# uC_Board.net
KiCad netlist of a schematic drawn in EAGLE
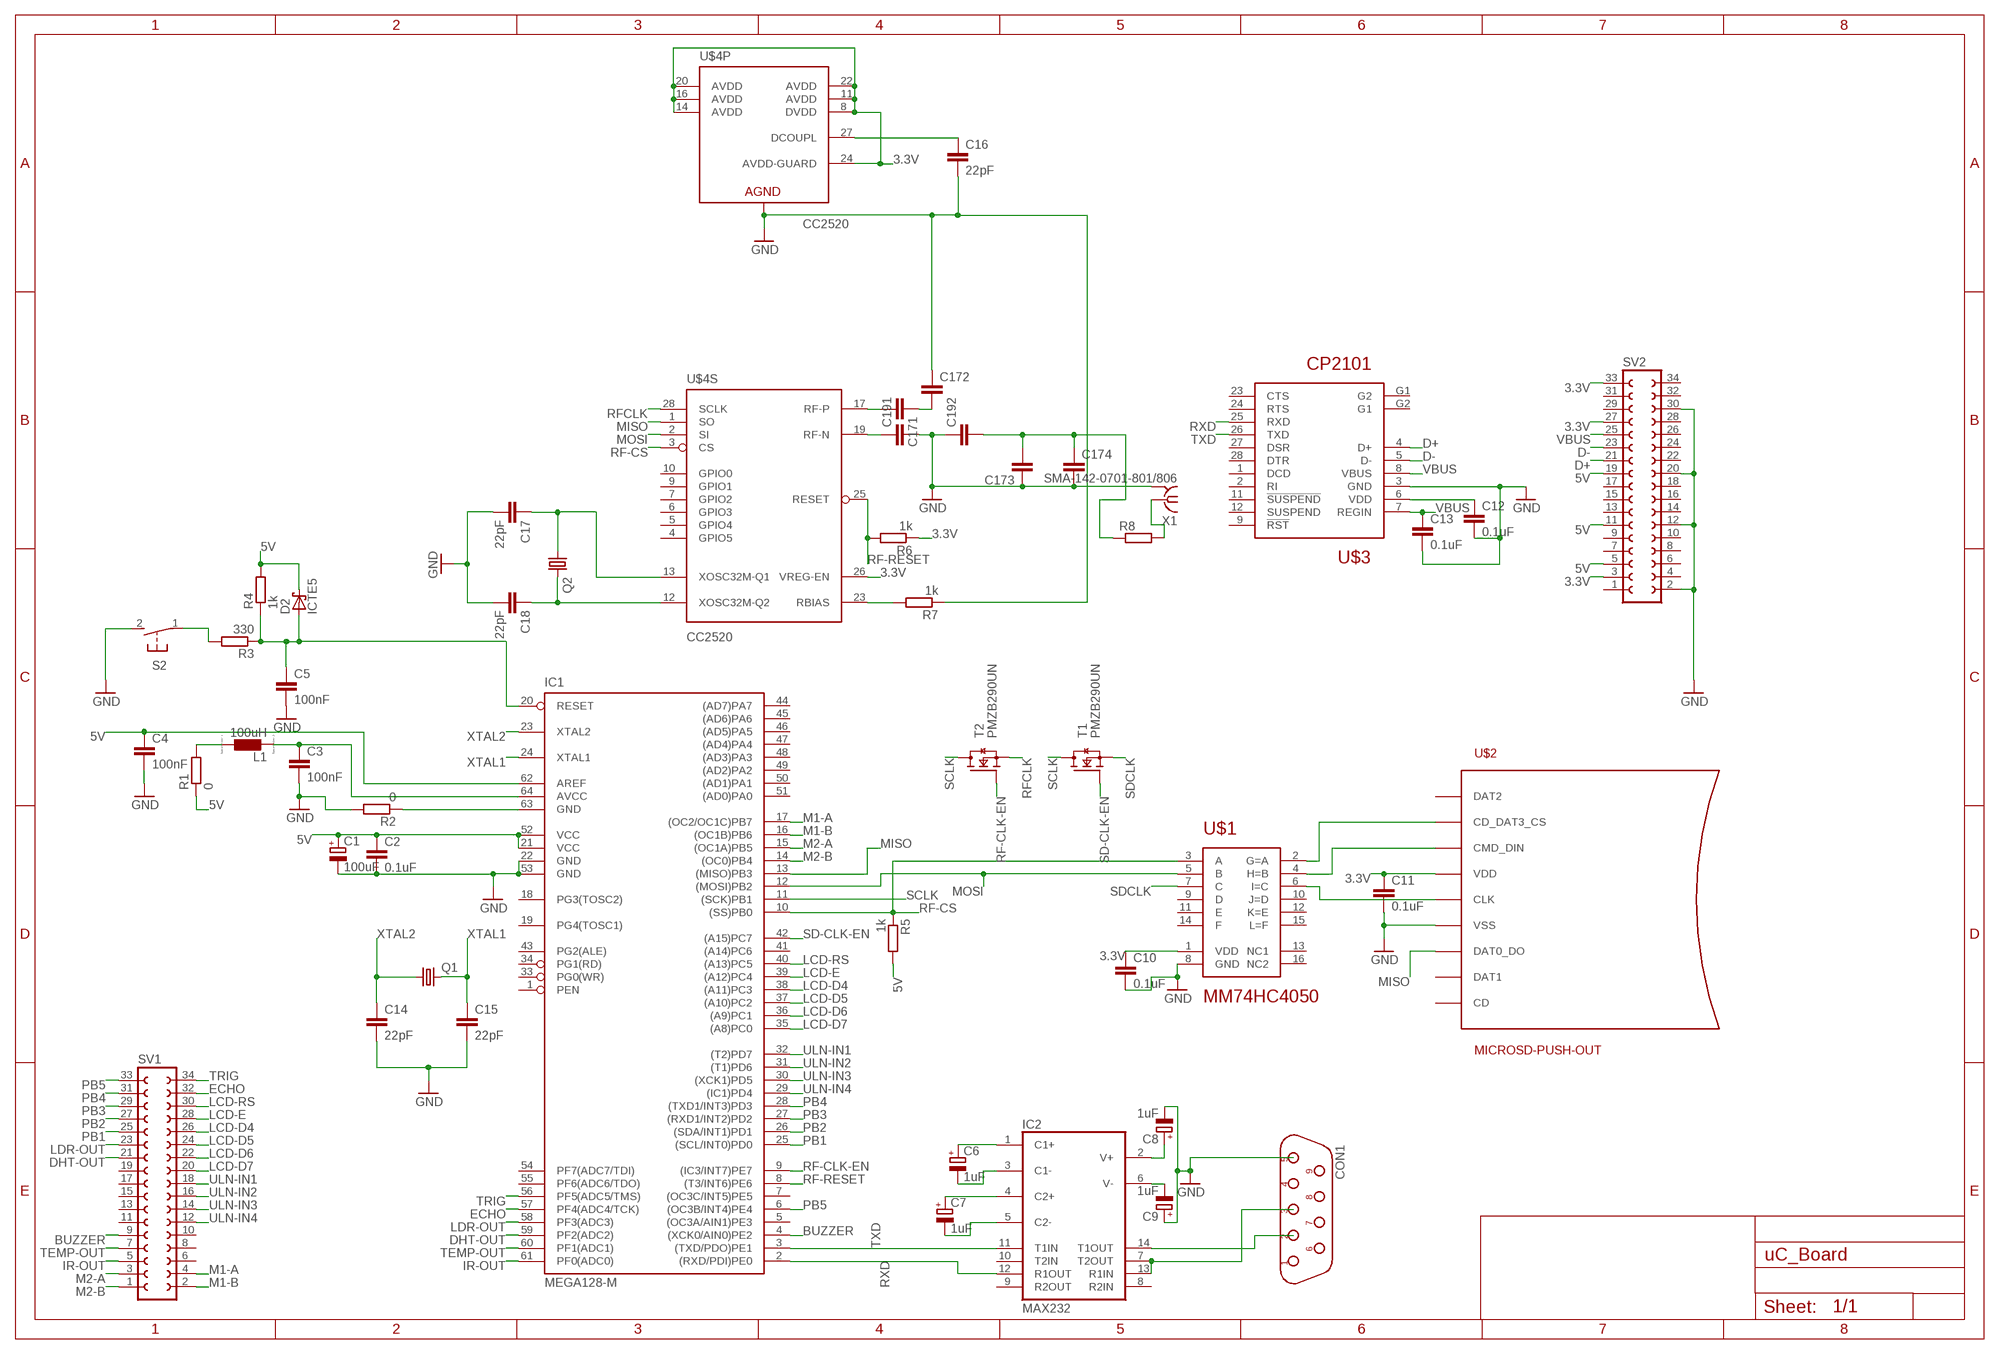
[diagram p0: schematic, sheet 1]

(export (version "E")
  (design (tool "Eeschema 10.0.6"))
  (components
    (comp (ref "C1")
      (value "100uF")
      (footprint "eagle-import:CT3528")
      (libsource (lib "eagle-import") (part "CPOL-EUCT3528"))
    )
    (comp (ref "C2")
      (value "0.1uF")
      (footprint "eagle-import:C0805")
      (libsource (lib "eagle-import") (part "C-EUC0805"))
    )
    (comp (ref "C3")
      (value "100nF")
      (footprint "eagle-import:C0805")
      (libsource (lib "eagle-import") (part "C-EUC0805"))
    )
    (comp (ref "C4")
      (value "100nF")
      (footprint "eagle-import:C0805")
      (libsource (lib "eagle-import") (part "C-EUC0805"))
    )
    (comp (ref "C5")
      (value "100nF")
      (footprint "eagle-import:C0805")
      (libsource (lib "eagle-import") (part "C-EUC0805"))
    )
    (comp (ref "C6")
      (value "1uF")
      (footprint "eagle-import:CT3528")
      (libsource (lib "eagle-import") (part "CPOL-EUCT3528"))
    )
    (comp (ref "C7")
      (value "1uF")
      (footprint "eagle-import:CT3528")
      (libsource (lib "eagle-import") (part "CPOL-EUCT3528"))
    )
    (comp (ref "C8")
      (value "1uF")
      (footprint "eagle-import:CT3528")
      (libsource (lib "eagle-import") (part "CPOL-EUCT3528"))
    )
    (comp (ref "C9")
      (value "1uF")
      (footprint "eagle-import:CT3528")
      (libsource (lib "eagle-import") (part "CPOL-EUCT3528"))
    )
    (comp (ref "C10")
      (value "0.1uF")
      (footprint "eagle-import:C0805")
      (libsource (lib "eagle-import") (part "C-EUC0805"))
    )
    (comp (ref "C11")
      (value "0.1uF")
      (footprint "eagle-import:C0805")
      (libsource (lib "eagle-import") (part "C-EUC0805"))
    )
    (comp (ref "C12")
      (value "0.1uF")
      (footprint "eagle-import:C0805")
      (libsource (lib "eagle-import") (part "C-EUC0805"))
    )
    (comp (ref "C13")
      (value "0.1uF")
      (footprint "eagle-import:C0805")
      (libsource (lib "eagle-import") (part "C-EUC0805"))
    )
    (comp (ref "C14")
      (value "22pF")
      (footprint "eagle-import:C0805")
      (libsource (lib "eagle-import") (part "C-EUC0805"))
    )
    (comp (ref "C15")
      (value "22pF")
      (footprint "eagle-import:C0805")
      (libsource (lib "eagle-import") (part "C-EUC0805"))
    )
    (comp (ref "C16")
      (value "22pF")
      (footprint "eagle-import:C0805")
      (libsource (lib "eagle-import") (part "C-EUC0805"))
    )
    (comp (ref "C17")
      (value "22pF")
      (footprint "eagle-import:C0805")
      (libsource (lib "eagle-import") (part "C-EUC0805"))
    )
    (comp (ref "C18")
      (value "22pF")
      (footprint "eagle-import:C0805")
      (libsource (lib "eagle-import") (part "C-EUC0805"))
    )
    (comp (ref "C171")
      (value "C-EUC0201")
      (footprint "eagle-import:C0201")
      (libsource (lib "eagle-import") (part "C-EUC0201"))
    )
    (comp (ref "C172")
      (value "C-EUC0201")
      (footprint "eagle-import:C0201")
      (libsource (lib "eagle-import") (part "C-EUC0201"))
    )
    (comp (ref "C173")
      (value "C-EUC0201")
      (footprint "eagle-import:C0201")
      (libsource (lib "eagle-import") (part "C-EUC0201"))
    )
    (comp (ref "C174")
      (value "C-EUC0201")
      (footprint "eagle-import:C0201")
      (libsource (lib "eagle-import") (part "C-EUC0201"))
    )
    (comp (ref "C191")
      (value "C-EUC0201")
      (footprint "eagle-import:C0201")
      (libsource (lib "eagle-import") (part "C-EUC0201"))
    )
    (comp (ref "C192")
      (value "C-EUC0201")
      (footprint "eagle-import:C0201")
      (libsource (lib "eagle-import") (part "C-EUC0201"))
    )
    (comp (ref "CON1")
      (value "DB9F")
      (footprint "eagle-import:D-09F")
      (libsource (lib "eagle-import") (part "DB9F"))
    )
    (comp (ref "D2")
      (value "ICTE5")
      (footprint "eagle-import:C4111-15")
      (libsource (lib "eagle-import") (part "ICTE5"))
    )
    (comp (ref "IC1")
      (value "MEGA128-M")
      (footprint "eagle-import:MLF64")
      (fields (field (name "MPN") "ATMEGA128-16MU"))
      (libsource (lib "eagle-import") (part "MEGA128-M"))
    )
    (comp (ref "IC2")
      (value "MAX232")
      (footprint "eagle-import:DIL16")
      (fields (field (name "MF") "MAXIM") (field (name "MPN") "MAX232ACPE+"))
      (libsource (lib "eagle-import") (part "MAX232"))
    )
    (comp (ref "L1")
      (value "100uH")
      (footprint "eagle-import:0207_10")
      (libsource (lib "eagle-import") (part "L0207/10"))
    )
    (comp (ref "Q1")
      (value "CRYSTALCTS406")
      (footprint "eagle-import:CTS406")
      (libsource (lib "eagle-import") (part "CRYSTALCTS406"))
    )
    (comp (ref "Q2")
      (value "CRYSTALCTS406")
      (footprint "eagle-import:CTS406")
      (libsource (lib "eagle-import") (part "CRYSTALCTS406"))
    )
    (comp (ref "R1")
      (value "0")
      (footprint "eagle-import:R0603")
      (libsource (lib "eagle-import") (part "R-EU_R0603"))
    )
    (comp (ref "R2")
      (value "0")
      (footprint "eagle-import:R0603")
      (libsource (lib "eagle-import") (part "R-EU_R0603"))
    )
    (comp (ref "R3")
      (value "330")
      (footprint "eagle-import:R0603")
      (libsource (lib "eagle-import") (part "R-EU_R0603"))
    )
    (comp (ref "R4")
      (value "1k")
      (footprint "eagle-import:R0603")
      (libsource (lib "eagle-import") (part "R-EU_R0603"))
    )
    (comp (ref "R5")
      (value "1k")
      (footprint "eagle-import:R0603")
      (libsource (lib "eagle-import") (part "R-EU_R0603"))
    )
    (comp (ref "R6")
      (value "1k")
      (footprint "eagle-import:R0603")
      (libsource (lib "eagle-import") (part "R-EU_R0603"))
    )
    (comp (ref "R7")
      (value "1k")
      (footprint "eagle-import:R0603")
      (libsource (lib "eagle-import") (part "R-EU_R0603"))
    )
    (comp (ref "R8")
      (value "R-EU_R0201")
      (footprint "eagle-import:R0201")
      (libsource (lib "eagle-import") (part "R-EU_R0201"))
    )
    (comp (ref "S2")
      (value "31-XX")
      (footprint "eagle-import:B3F-31XX")
      (fields (field (name "MPN") "B3F-3100"))
      (libsource (lib "eagle-import") (part "31-XX"))
    )
    (comp (ref "SV1")
      (value "FE17-2W")
      (footprint "eagle-import:FE17-2W")
      (libsource (lib "eagle-import") (part "FE17-2W"))
    )
    (comp (ref "SV2")
      (value "FE17-2W")
      (footprint "eagle-import:FE17-2W")
      (libsource (lib "eagle-import") (part "FE17-2W"))
    )
    (comp (ref "T1")
      (value "PMZB290UN")
      (footprint "eagle-import:SOT883(B)")
      (libsource (lib "eagle-import") (part "PMZB290UN"))
    )
    (comp (ref "T2")
      (value "PMZB290UN")
      (footprint "eagle-import:SOT883(B)")
      (libsource (lib "eagle-import") (part "PMZB290UN"))
    )
    (comp (ref "U$1")
      (value "MM74HC4050")
      (footprint "eagle-import:MM74HC4050")
      (libsource (lib "eagle-import") (part "MM74HC4050"))
    )
    (comp (ref "U$2")
      (value "MICROSD-PUSH-OUT")
      (footprint "eagle-import:MICROSD-PUSH-OUT")
      (libsource (lib "eagle-import") (part "MICROSD-PUSH-OUT"))
    )
    (comp (ref "U$3")
      (value "CP2101")
      (footprint "eagle-import:CP2101")
      (libsource (lib "eagle-import") (part "CP2101"))
    )
    (comp (ref "U$4")
      (value "CC2520")
      (footprint "eagle-import:QFN50P500X500X100-29N")
      (libsource (lib "eagle-import") (part "CC2520"))
    )
    (comp (ref "X1")
      (value "SMA-142-0701-801/806")
      (footprint "eagle-import:J502-ND-142-0701-801_806")
      (fields (field (name "MF") "JOHNSON COMPONENTS") (field (name "MPN") "142-0701-801"))
      (libsource (lib "eagle-import") (part "SMA-142-0701-801/806"))
    )
  )
  (nets
    (net (code "1") (name "/3.3V") (class "Default")
      (node (ref "C10") (pin "1") (pinfunction "1_1") (pintype "passive"))
      (node (ref "C11") (pin "1") (pinfunction "1_1") (pintype "passive"))
      (node (ref "R6") (pin "1") (pinfunction "1_1") (pintype "passive"))
      (node (ref "SV2") (pin "27") (pinfunction "27_27") (pintype "passive"))
      (node (ref "SV2") (pin "3") (pinfunction "3_3") (pintype "passive"))
      (node (ref "SV2") (pin "33") (pinfunction "33_33") (pintype "passive"))
      (node (ref "U$1") (pin "1") (pinfunction "VDD_1") (pintype "bidirectional"))
      (node (ref "U$2") (pin "4") (pinfunction "VDD_4") (pintype "bidirectional"))
      (node (ref "U$4") (pin "11") (pinfunction "AVDD_11") (pintype "power_in"))
      (node (ref "U$4") (pin "14") (pinfunction "AVDD_14") (pintype "power_in"))
      (node (ref "U$4") (pin "16") (pinfunction "AVDD_16") (pintype "power_in"))
      (node (ref "U$4") (pin "20") (pinfunction "AVDD_20") (pintype "power_in"))
      (node (ref "U$4") (pin "22") (pinfunction "AVDD_22") (pintype "power_in"))
      (node (ref "U$4") (pin "24") (pinfunction "AVDD-GUARD_24") (pintype "power_in"))
      (node (ref "U$4") (pin "26") (pinfunction "VREG-EN_26") (pintype "input"))
      (node (ref "U$4") (pin "8") (pinfunction "DVDD_8") (pintype "power_in"))
    )
    (net (code "2") (name "/5V") (class "Default")
      (node (ref "C1") (pin "+") (pinfunction "+_+") (pintype "passive"))
      (node (ref "C2") (pin "1") (pinfunction "1_1") (pintype "passive"))
      (node (ref "C4") (pin "1") (pinfunction "1_1") (pintype "passive"))
      (node (ref "D2") (pin "C") (pinfunction "C_C") (pintype "passive"))
      (node (ref "IC1") (pin "21") (pinfunction "VCC_21") (pintype "power_in"))
      (node (ref "IC1") (pin "52") (pinfunction "VCC_52") (pintype "power_in"))
      (node (ref "IC1") (pin "62") (pinfunction "AREF_62") (pintype "passive"))
      (node (ref "L1") (pin "1") (pinfunction "1_1") (pintype "passive"))
      (node (ref "R1") (pin "1") (pinfunction "1_1") (pintype "passive"))
      (node (ref "R1") (pin "2") (pinfunction "2_2") (pintype "passive"))
      (node (ref "R4") (pin "2") (pinfunction "2_2") (pintype "passive"))
      (node (ref "R5") (pin "2") (pinfunction "2_2") (pintype "passive"))
      (node (ref "SV2") (pin "11") (pinfunction "11_11") (pintype "passive"))
      (node (ref "SV2") (pin "19") (pinfunction "19_19") (pintype "passive"))
      (node (ref "SV2") (pin "5") (pinfunction "5_5") (pintype "passive"))
    )
    (net (code "3") (name "/BUZZER") (class "Default")
      (node (ref "IC1") (pin "4") (pinfunction "(XCK0/AIN0)PE2_4") (pintype "bidirectional"))
      (node (ref "SV1") (pin "9") (pinfunction "9_9") (pintype "passive"))
    )
    (net (code "4") (name "/D+") (class "Default")
      (node (ref "SV2") (pin "21") (pinfunction "21_21") (pintype "passive"))
      (node (ref "U$3") (pin "4") (pinfunction "D+_4") (pintype "bidirectional"))
    )
    (net (code "5") (name "/D-") (class "Default")
      (node (ref "SV2") (pin "23") (pinfunction "23_23") (pintype "passive"))
      (node (ref "U$3") (pin "5") (pinfunction "D-_5") (pintype "bidirectional"))
    )
    (net (code "6") (name "/DHT-OUT") (class "Default")
      (node (ref "IC1") (pin "59") (pinfunction "PF2(ADC2)_59") (pintype "input"))
      (node (ref "SV1") (pin "21") (pinfunction "21_21") (pintype "passive"))
    )
    (net (code "7") (name "/ECHO") (class "Default")
      (node (ref "IC1") (pin "57") (pinfunction "PF4(ADC4/TCK)_57") (pintype "input"))
      (node (ref "SV1") (pin "32") (pinfunction "32_32") (pintype "passive"))
    )
    (net (code "8") (name "/IR-OUT") (class "Default")
      (node (ref "IC1") (pin "61") (pinfunction "PF0(ADC0)_61") (pintype "input"))
      (node (ref "SV1") (pin "5") (pinfunction "5_5") (pintype "passive"))
    )
    (net (code "9") (name "/LCD-D4") (class "Default")
      (node (ref "IC1") (pin "38") (pinfunction "(A11)PC3_38") (pintype "output"))
      (node (ref "SV1") (pin "26") (pinfunction "26_26") (pintype "passive"))
    )
    (net (code "10") (name "/LCD-D5") (class "Default")
      (node (ref "IC1") (pin "37") (pinfunction "(A10)PC2_37") (pintype "output"))
      (node (ref "SV1") (pin "24") (pinfunction "24_24") (pintype "passive"))
    )
    (net (code "11") (name "/LCD-D6") (class "Default")
      (node (ref "IC1") (pin "36") (pinfunction "(A9)PC1_36") (pintype "output"))
      (node (ref "SV1") (pin "22") (pinfunction "22_22") (pintype "passive"))
    )
    (net (code "12") (name "/LCD-D7") (class "Default")
      (node (ref "IC1") (pin "35") (pinfunction "(A8)PC0_35") (pintype "output"))
      (node (ref "SV1") (pin "20") (pinfunction "20_20") (pintype "passive"))
    )
    (net (code "13") (name "/LCD-E") (class "Default")
      (node (ref "IC1") (pin "39") (pinfunction "(A12)PC4_39") (pintype "output"))
      (node (ref "SV1") (pin "28") (pinfunction "28_28") (pintype "passive"))
    )
    (net (code "14") (name "/LCD-RS") (class "Default")
      (node (ref "IC1") (pin "40") (pinfunction "(A13)PC5_40") (pintype "output"))
      (node (ref "SV1") (pin "30") (pinfunction "30_30") (pintype "passive"))
    )
    (net (code "15") (name "/LDR-OUT") (class "Default")
      (node (ref "IC1") (pin "58") (pinfunction "PF3(ADC3)_58") (pintype "input"))
      (node (ref "SV1") (pin "23") (pinfunction "23_23") (pintype "passive"))
    )
    (net (code "16") (name "/M1-A") (class "Default")
      (node (ref "IC1") (pin "17") (pinfunction "(OC2/OC1C)PB7_17") (pintype "bidirectional"))
      (node (ref "SV1") (pin "4") (pinfunction "4_4") (pintype "passive"))
    )
    (net (code "17") (name "/M1-B") (class "Default")
      (node (ref "IC1") (pin "16") (pinfunction "(OC1B)PB6_16") (pintype "bidirectional"))
      (node (ref "SV1") (pin "2") (pinfunction "2_2") (pintype "passive"))
    )
    (net (code "18") (name "/M2-A") (class "Default")
      (node (ref "IC1") (pin "15") (pinfunction "(OC1A)PB5_15") (pintype "bidirectional"))
      (node (ref "SV1") (pin "3") (pinfunction "3_3") (pintype "passive"))
    )
    (net (code "19") (name "/M2-B") (class "Default")
      (node (ref "IC1") (pin "14") (pinfunction "(OC0)PB4_14") (pintype "bidirectional"))
      (node (ref "SV1") (pin "1") (pinfunction "1_1") (pintype "passive"))
    )
    (net (code "20") (name "/MISO") (class "Default")
      (node (ref "IC1") (pin "13") (pinfunction "(MISO)PB3_13") (pintype "bidirectional"))
      (node (ref "U$2") (pin "7") (pinfunction "DAT0_DO_7") (pintype "bidirectional"))
      (node (ref "U$4") (pin "1") (pinfunction "SO_1") (pintype "output"))
    )
    (net (code "21") (name "/MOSI") (class "Default")
      (node (ref "IC1") (pin "12") (pinfunction "(MOSI)PB2_12") (pintype "bidirectional"))
      (node (ref "U$1") (pin "5") (pinfunction "B_5") (pintype "bidirectional"))
      (node (ref "U$4") (pin "2") (pinfunction "SI_2") (pintype "input"))
    )
    (net (code "22") (name "/PB1") (class "Default")
      (node (ref "IC1") (pin "25") (pinfunction "(SCL/INT0)PD0_25") (pintype "bidirectional"))
      (node (ref "SV1") (pin "25") (pinfunction "25_25") (pintype "passive"))
    )
    (net (code "23") (name "/PB2") (class "Default")
      (node (ref "IC1") (pin "26") (pinfunction "(SDA/INT1)PD1_26") (pintype "bidirectional"))
      (node (ref "SV1") (pin "27") (pinfunction "27_27") (pintype "passive"))
    )
    (net (code "24") (name "/PB3") (class "Default")
      (node (ref "IC1") (pin "27") (pinfunction "(RXD1/INT2)PD2_27") (pintype "bidirectional"))
      (node (ref "SV1") (pin "29") (pinfunction "29_29") (pintype "passive"))
    )
    (net (code "25") (name "/PB4") (class "Default")
      (node (ref "IC1") (pin "28") (pinfunction "(TXD1/INT3)PD3_28") (pintype "bidirectional"))
      (node (ref "SV1") (pin "31") (pinfunction "31_31") (pintype "passive"))
    )
    (net (code "26") (name "/PB5") (class "Default")
      (node (ref "IC1") (pin "6") (pinfunction "(OC3B/INT4)PE4_6") (pintype "bidirectional"))
      (node (ref "SV1") (pin "33") (pinfunction "33_33") (pintype "passive"))
    )
    (net (code "27") (name "/RF-CLK-EN") (class "Default")
      (node (ref "IC1") (pin "9") (pinfunction "(IC3/INT7)PE7_9") (pintype "bidirectional"))
      (node (ref "T2") (pin "1") (pinfunction "G_1") (pintype "passive"))
    )
    (net (code "28") (name "/RF-CS") (class "Default")
      (node (ref "IC1") (pin "10") (pinfunction "(SS)PB0_10") (pintype "bidirectional"))
      (node (ref "R5") (pin "1") (pinfunction "1_1") (pintype "passive"))
      (node (ref "U$1") (pin "3") (pinfunction "A_3") (pintype "bidirectional"))
      (node (ref "U$4") (pin "3") (pinfunction "CS_3") (pintype "input"))
    )
    (net (code "29") (name "/RF-RESET") (class "Default")
      (node (ref "IC1") (pin "8") (pinfunction "(T3/INT6)PE6_8") (pintype "bidirectional"))
      (node (ref "R6") (pin "2") (pinfunction "2_2") (pintype "passive"))
      (node (ref "U$4") (pin "25") (pinfunction "RESET_25") (pintype "input"))
    )
    (net (code "30") (name "/RFCLK") (class "Default")
      (node (ref "T2") (pin "2") (pinfunction "S_2") (pintype "passive"))
      (node (ref "U$4") (pin "28") (pinfunction "SCLK_28") (pintype "input"))
    )
    (net (code "31") (name "/RXD") (class "Default")
      (node (ref "IC1") (pin "2") (pinfunction "(RXD/PDI)PE0_2") (pintype "bidirectional"))
      (node (ref "IC2") (pin "12") (pinfunction "R1OUT_12") (pintype "output"))
      (node (ref "U$3") (pin "25") (pinfunction "RXD_25") (pintype "bidirectional"))
    )
    (net (code "32") (name "/SCLK") (class "Default")
      (node (ref "IC1") (pin "11") (pinfunction "(SCK)PB1_11") (pintype "bidirectional"))
      (node (ref "T1") (pin "3") (pinfunction "D_3") (pintype "passive"))
      (node (ref "T2") (pin "3") (pinfunction "D_3") (pintype "passive"))
    )
    (net (code "33") (name "/SD-CLK-EN") (class "Default")
      (node (ref "IC1") (pin "42") (pinfunction "(A15)PC7_42") (pintype "output"))
      (node (ref "T1") (pin "1") (pinfunction "G_1") (pintype "passive"))
    )
    (net (code "34") (name "/SDCLK") (class "Default")
      (node (ref "T1") (pin "2") (pinfunction "S_2") (pintype "passive"))
      (node (ref "U$1") (pin "7") (pinfunction "C_7") (pintype "bidirectional"))
    )
    (net (code "35") (name "/TEMP-OUT") (class "Default")
      (node (ref "IC1") (pin "60") (pinfunction "PF1(ADC1)_60") (pintype "input"))
      (node (ref "SV1") (pin "7") (pinfunction "7_7") (pintype "passive"))
    )
    (net (code "36") (name "/TRIG") (class "Default")
      (node (ref "IC1") (pin "56") (pinfunction "PF5(ADC5/TMS)_56") (pintype "input"))
      (node (ref "SV1") (pin "34") (pinfunction "34_34") (pintype "passive"))
    )
    (net (code "37") (name "/TXD") (class "Default")
      (node (ref "IC1") (pin "3") (pinfunction "(TXD/PDO)PE1_3") (pintype "bidirectional"))
      (node (ref "IC2") (pin "11") (pinfunction "T1IN_11") (pintype "input"))
      (node (ref "U$3") (pin "26") (pinfunction "TXD_26") (pintype "bidirectional"))
    )
    (net (code "38") (name "/ULN-IN1") (class "Default")
      (node (ref "IC1") (pin "32") (pinfunction "(T2)PD7_32") (pintype "bidirectional"))
      (node (ref "SV1") (pin "18") (pinfunction "18_18") (pintype "passive"))
    )
    (net (code "39") (name "/ULN-IN2") (class "Default")
      (node (ref "IC1") (pin "31") (pinfunction "(T1)PD6_31") (pintype "bidirectional"))
      (node (ref "SV1") (pin "16") (pinfunction "16_16") (pintype "passive"))
    )
    (net (code "40") (name "/ULN-IN3") (class "Default")
      (node (ref "IC1") (pin "30") (pinfunction "(XCK1)PD5_30") (pintype "bidirectional"))
      (node (ref "SV1") (pin "14") (pinfunction "14_14") (pintype "passive"))
    )
    (net (code "41") (name "/ULN-IN4") (class "Default")
      (node (ref "IC1") (pin "29") (pinfunction "(IC1)PD4_29") (pintype "bidirectional"))
      (node (ref "SV1") (pin "12") (pinfunction "12_12") (pintype "passive"))
    )
    (net (code "42") (name "/VBUS") (class "Default")
      (node (ref "C13") (pin "1") (pinfunction "1_1") (pintype "passive"))
      (node (ref "SV2") (pin "25") (pinfunction "25_25") (pintype "passive"))
      (node (ref "U$3") (pin "7") (pinfunction "REGIN_7") (pintype "bidirectional"))
      (node (ref "U$3") (pin "8") (pinfunction "VBUS_8") (pintype "bidirectional"))
    )
    (net (code "43") (name "/XTAL1") (class "Default")
      (node (ref "C15") (pin "1") (pinfunction "1_1") (pintype "passive"))
      (node (ref "IC1") (pin "24") (pinfunction "XTAL1_24") (pintype "bidirectional"))
      (node (ref "Q1") (pin "3") (pinfunction "2_3") (pintype "passive"))
    )
    (net (code "44") (name "/XTAL2") (class "Default")
      (node (ref "C14") (pin "1") (pinfunction "1_1") (pintype "passive"))
      (node (ref "IC1") (pin "23") (pinfunction "XTAL2_23") (pintype "bidirectional"))
      (node (ref "Q1") (pin "1") (pinfunction "1_1") (pintype "passive"))
    )
    (net (code "45") (name "GND") (class "Default")
      (node (ref "C1") (pin "-") (pinfunction "-_-") (pintype "passive"))
      (node (ref "C10") (pin "2") (pinfunction "2_2") (pintype "passive"))
      (node (ref "C11") (pin "2") (pinfunction "2_2") (pintype "passive"))
      (node (ref "C12") (pin "2") (pinfunction "2_2") (pintype "passive"))
      (node (ref "C13") (pin "2") (pinfunction "2_2") (pintype "passive"))
      (node (ref "C14") (pin "2") (pinfunction "2_2") (pintype "passive"))
      (node (ref "C15") (pin "2") (pinfunction "2_2") (pintype "passive"))
      (node (ref "C16") (pin "2") (pinfunction "2_2") (pintype "passive"))
      (node (ref "C17") (pin "2") (pinfunction "2_2") (pintype "passive"))
      (node (ref "C172") (pin "1") (pinfunction "1_1") (pintype "passive"))
      (node (ref "C173") (pin "1") (pinfunction "1_1") (pintype "passive"))
      (node (ref "C174") (pin "2") (pinfunction "2_2") (pintype "passive"))
      (node (ref "C18") (pin "2") (pinfunction "2_2") (pintype "passive"))
      (node (ref "C191") (pin "2") (pinfunction "2_2") (pintype "passive"))
      (node (ref "C192") (pin "1") (pinfunction "1_1") (pintype "passive"))
      (node (ref "C2") (pin "2") (pinfunction "2_2") (pintype "passive"))
      (node (ref "C3") (pin "2") (pinfunction "2_2") (pintype "passive"))
      (node (ref "C4") (pin "2") (pinfunction "2_2") (pintype "passive"))
      (node (ref "C5") (pin "2") (pinfunction "2_2") (pintype "passive"))
      (node (ref "C8") (pin "-") (pinfunction "-_-") (pintype "passive"))
      (node (ref "C9") (pin "+") (pinfunction "+_+") (pintype "passive"))
      (node (ref "CON1") (pin "5") (pinfunction "5_5") (pintype "passive"))
      (node (ref "IC1") (pin "22") (pinfunction "GND_22") (pintype "power_in"))
      (node (ref "IC1") (pin "53") (pinfunction "GND_53") (pintype "power_in"))
      (node (ref "R2") (pin "2") (pinfunction "2_2") (pintype "passive"))
      (node (ref "R7") (pin "1") (pinfunction "1_1") (pintype "passive"))
      (node (ref "S2") (pin "2") (pinfunction "S_2") (pintype "passive"))
      (node (ref "SV2") (pin "12") (pinfunction "12_12") (pintype "passive"))
      (node (ref "SV2") (pin "2") (pinfunction "2_2") (pintype "passive"))
      (node (ref "SV2") (pin "20") (pinfunction "20_20") (pintype "passive"))
      (node (ref "SV2") (pin "30") (pinfunction "30_30") (pintype "passive"))
      (node (ref "U$1") (pin "8") (pinfunction "GND_8") (pintype "bidirectional"))
      (node (ref "U$2") (pin "6") (pinfunction "VSS_6") (pintype "bidirectional"))
      (node (ref "U$2") (pin "G1") (pinfunction "VSS_G1") (pintype "bidirectional"))
      (node (ref "U$2") (pin "G2") (pinfunction "VSS_G2") (pintype "bidirectional"))
      (node (ref "U$2") (pin "G3") (pinfunction "VSS_G3") (pintype "bidirectional"))
      (node (ref "U$2") (pin "G4") (pinfunction "VSS_G4") (pintype "bidirectional"))
      (node (ref "U$3") (pin "3") (pinfunction "GND_3") (pintype "bidirectional"))
      (node (ref "U$4") (pin "29") (pinfunction "AGND_29") (pintype "power_in"))
      (node (ref "X1") (pin "G@1") (pinfunction "2_G@1") (pintype "passive"))
      (node (ref "X1") (pin "G@2") (pinfunction "2_G@2") (pintype "passive"))
      (node (ref "X1") (pin "G@3") (pinfunction "2_G@3") (pintype "passive"))
      (node (ref "X1") (pin "G@4") (pinfunction "2_G@4") (pintype "passive"))
    )
    (net (code "46") (name "Net-(C171-Pad1)") (class "Default")
      (node (ref "C171") (pin "1") (pinfunction "1_1") (pintype "passive"))
      (node (ref "C172") (pin "2") (pinfunction "2_2") (pintype "passive"))
    )
    (net (code "47") (name "Net-(C173-Pad2)") (class "Default")
      (node (ref "C173") (pin "2") (pinfunction "2_2") (pintype "passive"))
      (node (ref "C174") (pin "1") (pinfunction "1_1") (pintype "passive"))
      (node (ref "C192") (pin "2") (pinfunction "2_2") (pintype "passive"))
      (node (ref "R8") (pin "1") (pinfunction "1_1") (pintype "passive"))
    )
    (net (code "48") (name "Net-(IC1-AVCC)") (class "Default")
      (node (ref "C3") (pin "1") (pinfunction "1_1") (pintype "passive"))
      (node (ref "IC1") (pin "64") (pinfunction "AVCC_64") (pintype "power_in"))
      (node (ref "L1") (pin "2") (pinfunction "2_2") (pintype "passive"))
    )
    (net (code "49") (name "Net-(IC1-GND-Pad63)") (class "Default")
      (node (ref "IC1") (pin "63") (pinfunction "GND_63") (pintype "power_in"))
      (node (ref "R2") (pin "1") (pinfunction "1_1") (pintype "passive"))
    )
    (net (code "50") (name "Net-(IC1-RESET)") (class "Default")
      (node (ref "C5") (pin "1") (pinfunction "1_1") (pintype "passive"))
      (node (ref "D2") (pin "A") (pinfunction "A_A") (pintype "passive"))
      (node (ref "IC1") (pin "20") (pinfunction "RESET_20") (pintype "input"))
      (node (ref "R3") (pin "1") (pinfunction "1_1") (pintype "passive"))
      (node (ref "R4") (pin "1") (pinfunction "1_1") (pintype "passive"))
    )
    (net (code "51") (name "Net-(IC2A-C1+)") (class "Default")
      (node (ref "C6") (pin "+") (pinfunction "+_+") (pintype "passive"))
      (node (ref "IC2") (pin "1") (pinfunction "C1+_1") (pintype "bidirectional"))
    )
    (net (code "52") (name "Net-(IC2A-C1-)") (class "Default")
      (node (ref "C6") (pin "-") (pinfunction "-_-") (pintype "passive"))
      (node (ref "IC2") (pin "3") (pinfunction "C1-_3") (pintype "bidirectional"))
    )
    (net (code "53") (name "Net-(IC2A-C2+)") (class "Default")
      (node (ref "C7") (pin "+") (pinfunction "+_+") (pintype "passive"))
      (node (ref "IC2") (pin "4") (pinfunction "C2+_4") (pintype "bidirectional"))
    )
    (net (code "54") (name "Net-(IC2A-C2-)") (class "Default")
      (node (ref "C7") (pin "-") (pinfunction "-_-") (pintype "passive"))
      (node (ref "IC2") (pin "5") (pinfunction "C2-_5") (pintype "bidirectional"))
    )
    (net (code "55") (name "Net-(IC2A-R1IN)") (class "Default")
      (node (ref "CON1") (pin "3") (pinfunction "3_3") (pintype "passive"))
      (node (ref "IC2") (pin "13") (pinfunction "R1IN_13") (pintype "input"))
      (node (ref "IC2") (pin "7") (pinfunction "T2OUT_7") (pintype "output"))
    )
    (net (code "56") (name "Net-(IC2A-T1OUT)") (class "Default")
      (node (ref "CON1") (pin "2") (pinfunction "2_2") (pintype "passive"))
      (node (ref "IC2") (pin "14") (pinfunction "T1OUT_14") (pintype "output"))
    )
    (net (code "57") (name "Net-(IC2A-V+)") (class "Default")
      (node (ref "C8") (pin "+") (pinfunction "+_+") (pintype "passive"))
      (node (ref "IC2") (pin "2") (pinfunction "V+_2") (pintype "bidirectional"))
    )
    (net (code "58") (name "Net-(IC2A-V-)") (class "Default")
      (node (ref "C9") (pin "-") (pinfunction "-_-") (pintype "passive"))
      (node (ref "IC2") (pin "6") (pinfunction "V-_6") (pintype "bidirectional"))
    )
    (net (code "59") (name "Net-(Q2-2)") (class "Default")
      (node (ref "C18") (pin "1") (pinfunction "1_1") (pintype "passive"))
      (node (ref "Q2") (pin "3") (pinfunction "2_3") (pintype "passive"))
      (node (ref "U$4") (pin "12") (pinfunction "XOSC32M-Q2_12") (pintype "output"))
    )
    (net (code "60") (name "Net-(R8-Pad2)") (class "Default")
      (node (ref "R8") (pin "2") (pinfunction "2_2") (pintype "passive"))
      (node (ref "X1") (pin "1") (pinfunction "1_1") (pintype "passive"))
    )
    (net (code "61") (name "Net-(S2-P)") (class "Default")
      (node (ref "R3") (pin "2") (pinfunction "2_2") (pintype "passive"))
      (node (ref "S2") (pin "1") (pinfunction "P_1") (pintype "passive"))
    )
    (net (code "62") (name "Net-(U$1-G=A)") (class "Default")
      (node (ref "U$1") (pin "2") (pinfunction "G=A_2") (pintype "bidirectional"))
      (node (ref "U$2") (pin "2") (pinfunction "CD_DAT3_CS_2") (pintype "bidirectional"))
    )
    (net (code "63") (name "Net-(U$1-H=B)") (class "Default")
      (node (ref "U$1") (pin "4") (pinfunction "H=B_4") (pintype "bidirectional"))
      (node (ref "U$2") (pin "3") (pinfunction "CMD_DIN_3") (pintype "bidirectional"))
    )
    (net (code "64") (name "Net-(U$1-I=C)") (class "Default")
      (node (ref "U$1") (pin "6") (pinfunction "I=C_6") (pintype "bidirectional"))
      (node (ref "U$2") (pin "5") (pinfunction "CLK_5") (pintype "bidirectional"))
    )
    (net (code "65") (name "Net-(U$3-VDD)") (class "Default")
      (node (ref "C12") (pin "1") (pinfunction "1_1") (pintype "passive"))
      (node (ref "U$3") (pin "6") (pinfunction "VDD_6") (pintype "bidirectional"))
    )
    (net (code "66") (name "Net-(U$4B-DCOUPL)") (class "Default")
      (node (ref "C16") (pin "1") (pinfunction "1_1") (pintype "passive"))
      (node (ref "U$4") (pin "27") (pinfunction "DCOUPL_27") (pintype "power_in"))
    )
    (net (code "67") (name "Net-(U$4C-RBIAS)") (class "Default")
      (node (ref "R7") (pin "2") (pinfunction "2_2") (pintype "passive"))
      (node (ref "U$4") (pin "23") (pinfunction "RBIAS_23") (pintype "bidirectional"))
    )
    (net (code "68") (name "Net-(U$4C-RF-N)") (class "Default")
      (node (ref "C191") (pin "1") (pinfunction "1_1") (pintype "passive"))
      (node (ref "U$4") (pin "19") (pinfunction "RF-N_19") (pintype "bidirectional"))
    )
    (net (code "69") (name "Net-(U$4C-RF-P)") (class "Default")
      (node (ref "C171") (pin "2") (pinfunction "2_2") (pintype "passive"))
      (node (ref "U$4") (pin "17") (pinfunction "RF-P_17") (pintype "bidirectional"))
    )
    (net (code "70") (name "Net-(U$4C-XOSC32M-Q1)") (class "Default")
      (node (ref "C17") (pin "1") (pinfunction "1_1") (pintype "passive"))
      (node (ref "Q2") (pin "1") (pinfunction "1_1") (pintype "passive"))
      (node (ref "U$4") (pin "13") (pinfunction "XOSC32M-Q1_13") (pintype "input"))
    )
    (net (code "71") (name "unconnected-(CON1-Pad1)") (class "Default")
      (node (ref "CON1") (pin "1") (pinfunction "1_1") (pintype "passive"))
    )
    (net (code "72") (name "unconnected-(CON1-Pad4)") (class "Default")
      (node (ref "CON1") (pin "4") (pinfunction "4_4") (pintype "passive"))
    )
    (net (code "73") (name "unconnected-(CON1-Pad6)") (class "Default")
      (node (ref "CON1") (pin "6") (pinfunction "6_6") (pintype "passive"))
    )
    (net (code "74") (name "unconnected-(CON1-Pad7)") (class "Default")
      (node (ref "CON1") (pin "7") (pinfunction "7_7") (pintype "passive"))
    )
    (net (code "75") (name "unconnected-(CON1-Pad8)") (class "Default")
      (node (ref "CON1") (pin "8") (pinfunction "8_8") (pintype "passive"))
    )
    (net (code "76") (name "unconnected-(CON1-Pad9)") (class "Default")
      (node (ref "CON1") (pin "9") (pinfunction "9_9") (pintype "passive"))
    )
    (net (code "77") (name "unconnected-(IC1-(A14)PC6-Pad41)") (class "Default")
      (node (ref "IC1") (pin "41") (pinfunction "(A14)PC6_41") (pintype "output"))
    )
    (net (code "78") (name "unconnected-(IC1-(AD0)PA0-Pad51)") (class "Default")
      (node (ref "IC1") (pin "51") (pinfunction "(AD0)PA0_51") (pintype "bidirectional"))
    )
    (net (code "79") (name "unconnected-(IC1-(AD1)PA1-Pad50)") (class "Default")
      (node (ref "IC1") (pin "50") (pinfunction "(AD1)PA1_50") (pintype "bidirectional"))
    )
    (net (code "80") (name "unconnected-(IC1-(AD2)PA2-Pad49)") (class "Default")
      (node (ref "IC1") (pin "49") (pinfunction "(AD2)PA2_49") (pintype "bidirectional"))
    )
    (net (code "81") (name "unconnected-(IC1-(AD3)PA3-Pad48)") (class "Default")
      (node (ref "IC1") (pin "48") (pinfunction "(AD3)PA3_48") (pintype "bidirectional"))
    )
    (net (code "82") (name "unconnected-(IC1-(AD4)PA4-Pad47)") (class "Default")
      (node (ref "IC1") (pin "47") (pinfunction "(AD4)PA4_47") (pintype "bidirectional"))
    )
    (net (code "83") (name "unconnected-(IC1-(AD5)PA5-Pad46)") (class "Default")
      (node (ref "IC1") (pin "46") (pinfunction "(AD5)PA5_46") (pintype "bidirectional"))
    )
    (net (code "84") (name "unconnected-(IC1-(AD6)PA6-Pad45)") (class "Default")
      (node (ref "IC1") (pin "45") (pinfunction "(AD6)PA6_45") (pintype "bidirectional"))
    )
    (net (code "85") (name "unconnected-(IC1-(AD7)PA7-Pad44)") (class "Default")
      (node (ref "IC1") (pin "44") (pinfunction "(AD7)PA7_44") (pintype "bidirectional"))
    )
    (net (code "86") (name "unconnected-(IC1-(OC3A{slash}AIN1)PE3-Pad5)") (class "Default")
      (node (ref "IC1") (pin "5") (pinfunction "(OC3A/AIN1)PE3_5") (pintype "bidirectional"))
    )
    (net (code "87") (name "unconnected-(IC1-(OC3C{slash}INT5)PE5-Pad7)") (class "Default")
      (node (ref "IC1") (pin "7") (pinfunction "(OC3C/INT5)PE5_7") (pintype "bidirectional"))
    )
    (net (code "88") (name "unconnected-(IC1-PEN-Pad1)") (class "Default")
      (node (ref "IC1") (pin "1") (pinfunction "PEN_1") (pintype "input"))
    )
    (net (code "89") (name "unconnected-(IC1-PF6(ADC6{slash}TDO)-Pad55)") (class "Default")
      (node (ref "IC1") (pin "55") (pinfunction "PF6(ADC6/TDO)_55") (pintype "input"))
    )
    (net (code "90") (name "unconnected-(IC1-PF7(ADC7{slash}TDI)-Pad54)") (class "Default")
      (node (ref "IC1") (pin "54") (pinfunction "PF7(ADC7/TDI)_54") (pintype "input"))
    )
    (net (code "91") (name "unconnected-(IC1-PG0(WR)-Pad33)") (class "Default")
      (node (ref "IC1") (pin "33") (pinfunction "PG0(WR)_33") (pintype "bidirectional"))
    )
    (net (code "92") (name "unconnected-(IC1-PG1(RD)-Pad34)") (class "Default")
      (node (ref "IC1") (pin "34") (pinfunction "PG1(RD)_34") (pintype "bidirectional"))
    )
    (net (code "93") (name "unconnected-(IC1-PG2(ALE)-Pad43)") (class "Default")
      (node (ref "IC1") (pin "43") (pinfunction "PG2(ALE)_43") (pintype "bidirectional"))
    )
    (net (code "94") (name "unconnected-(IC1-PG3(TOSC2)-Pad18)") (class "Default")
      (node (ref "IC1") (pin "18") (pinfunction "PG3(TOSC2)_18") (pintype "bidirectional"))
    )
    (net (code "95") (name "unconnected-(IC1-PG4(TOSC1)-Pad19)") (class "Default")
      (node (ref "IC1") (pin "19") (pinfunction "PG4(TOSC1)_19") (pintype "bidirectional"))
    )
    (net (code "96") (name "unconnected-(IC2A-R2IN-Pad8)") (class "Default")
      (node (ref "IC2") (pin "8") (pinfunction "R2IN_8") (pintype "input"))
    )
    (net (code "97") (name "unconnected-(IC2A-R2OUT-Pad9)") (class "Default")
      (node (ref "IC2") (pin "9") (pinfunction "R2OUT_9") (pintype "output"))
    )
    (net (code "98") (name "unconnected-(IC2A-T2IN-Pad10)") (class "Default")
      (node (ref "IC2") (pin "10") (pinfunction "T2IN_10") (pintype "input"))
    )
    (net (code "99") (name "unconnected-(SV1-Pad6)") (class "Default")
      (node (ref "SV1") (pin "6") (pinfunction "6_6") (pintype "passive"))
    )
    (net (code "100") (name "unconnected-(SV1-Pad8)") (class "Default")
      (node (ref "SV1") (pin "8") (pinfunction "8_8") (pintype "passive"))
    )
    (net (code "101") (name "unconnected-(SV1-Pad10)") (class "Default")
      (node (ref "SV1") (pin "10") (pinfunction "10_10") (pintype "passive"))
    )
    (net (code "102") (name "unconnected-(SV1-Pad11)") (class "Default")
      (node (ref "SV1") (pin "11") (pinfunction "11_11") (pintype "passive"))
    )
    (net (code "103") (name "unconnected-(SV1-Pad13)") (class "Default")
      (node (ref "SV1") (pin "13") (pinfunction "13_13") (pintype "passive"))
    )
    (net (code "104") (name "unconnected-(SV1-Pad15)") (class "Default")
      (node (ref "SV1") (pin "15") (pinfunction "15_15") (pintype "passive"))
    )
    (net (code "105") (name "unconnected-(SV1-Pad17)") (class "Default")
      (node (ref "SV1") (pin "17") (pinfunction "17_17") (pintype "passive"))
    )
    (net (code "106") (name "unconnected-(SV1-Pad19)") (class "Default")
      (node (ref "SV1") (pin "19") (pinfunction "19_19") (pintype "passive"))
    )
    (net (code "107") (name "unconnected-(SV2-Pad1)") (class "Default")
      (node (ref "SV2") (pin "1") (pinfunction "1_1") (pintype "passive"))
    )
    (net (code "108") (name "unconnected-(SV2-Pad4)") (class "Default")
      (node (ref "SV2") (pin "4") (pinfunction "4_4") (pintype "passive"))
    )
    (net (code "109") (name "unconnected-(SV2-Pad6)") (class "Default")
      (node (ref "SV2") (pin "6") (pinfunction "6_6") (pintype "passive"))
    )
    (net (code "110") (name "unconnected-(SV2-Pad7)") (class "Default")
      (node (ref "SV2") (pin "7") (pinfunction "7_7") (pintype "passive"))
    )
    (net (code "111") (name "unconnected-(SV2-Pad8)") (class "Default")
      (node (ref "SV2") (pin "8") (pinfunction "8_8") (pintype "passive"))
    )
    (net (code "112") (name "unconnected-(SV2-Pad9)") (class "Default")
      (node (ref "SV2") (pin "9") (pinfunction "9_9") (pintype "passive"))
    )
    (net (code "113") (name "unconnected-(SV2-Pad10)") (class "Default")
      (node (ref "SV2") (pin "10") (pinfunction "10_10") (pintype "passive"))
    )
    (net (code "114") (name "unconnected-(SV2-Pad13)") (class "Default")
      (node (ref "SV2") (pin "13") (pinfunction "13_13") (pintype "passive"))
    )
    (net (code "115") (name "unconnected-(SV2-Pad14)") (class "Default")
      (node (ref "SV2") (pin "14") (pinfunction "14_14") (pintype "passive"))
    )
    (net (code "116") (name "unconnected-(SV2-Pad15)") (class "Default")
      (node (ref "SV2") (pin "15") (pinfunction "15_15") (pintype "passive"))
    )
    (net (code "117") (name "unconnected-(SV2-Pad16)") (class "Default")
      (node (ref "SV2") (pin "16") (pinfunction "16_16") (pintype "passive"))
    )
    (net (code "118") (name "unconnected-(SV2-Pad17)") (class "Default")
      (node (ref "SV2") (pin "17") (pinfunction "17_17") (pintype "passive"))
    )
    (net (code "119") (name "unconnected-(SV2-Pad18)") (class "Default")
      (node (ref "SV2") (pin "18") (pinfunction "18_18") (pintype "passive"))
    )
    (net (code "120") (name "unconnected-(SV2-Pad22)") (class "Default")
      (node (ref "SV2") (pin "22") (pinfunction "22_22") (pintype "passive"))
    )
    (net (code "121") (name "unconnected-(SV2-Pad24)") (class "Default")
      (node (ref "SV2") (pin "24") (pinfunction "24_24") (pintype "passive"))
    )
    (net (code "122") (name "unconnected-(SV2-Pad26)") (class "Default")
      (node (ref "SV2") (pin "26") (pinfunction "26_26") (pintype "passive"))
    )
    (net (code "123") (name "unconnected-(SV2-Pad28)") (class "Default")
      (node (ref "SV2") (pin "28") (pinfunction "28_28") (pintype "passive"))
    )
    (net (code "124") (name "unconnected-(SV2-Pad29)") (class "Default")
      (node (ref "SV2") (pin "29") (pinfunction "29_29") (pintype "passive"))
    )
    (net (code "125") (name "unconnected-(SV2-Pad31)") (class "Default")
      (node (ref "SV2") (pin "31") (pinfunction "31_31") (pintype "passive"))
    )
    (net (code "126") (name "unconnected-(SV2-Pad32)") (class "Default")
      (node (ref "SV2") (pin "32") (pinfunction "32_32") (pintype "passive"))
    )
    (net (code "127") (name "unconnected-(SV2-Pad34)") (class "Default")
      (node (ref "SV2") (pin "34") (pinfunction "34_34") (pintype "passive"))
    )
    (net (code "128") (name "unconnected-(U$1-D-Pad9)") (class "Default")
      (node (ref "U$1") (pin "9") (pinfunction "D_9") (pintype "bidirectional"))
    )
    (net (code "129") (name "unconnected-(U$1-E-Pad11)") (class "Default")
      (node (ref "U$1") (pin "11") (pinfunction "E_11") (pintype "bidirectional"))
    )
    (net (code "130") (name "unconnected-(U$1-F-Pad14)") (class "Default")
      (node (ref "U$1") (pin "14") (pinfunction "F_14") (pintype "bidirectional"))
    )
    (net (code "131") (name "unconnected-(U$1-J=D-Pad10)") (class "Default")
      (node (ref "U$1") (pin "10") (pinfunction "J=D_10") (pintype "bidirectional"))
    )
    (net (code "132") (name "unconnected-(U$1-K=E-Pad12)") (class "Default")
      (node (ref "U$1") (pin "12") (pinfunction "K=E_12") (pintype "bidirectional"))
    )
    (net (code "133") (name "unconnected-(U$1-L=F-Pad15)") (class "Default")
      (node (ref "U$1") (pin "15") (pinfunction "L=F_15") (pintype "bidirectional"))
    )
    (net (code "134") (name "unconnected-(U$1-NC1-Pad13)") (class "Default")
      (node (ref "U$1") (pin "13") (pinfunction "NC1_13") (pintype "bidirectional"))
    )
    (net (code "135") (name "unconnected-(U$1-NC2-Pad16)") (class "Default")
      (node (ref "U$1") (pin "16") (pinfunction "NC2_16") (pintype "bidirectional"))
    )
    (net (code "136") (name "unconnected-(U$2-DAT1-Pad8)") (class "Default")
      (node (ref "U$2") (pin "8") (pinfunction "DAT1_8") (pintype "bidirectional"))
    )
    (net (code "137") (name "unconnected-(U$2-DAT2-Pad1)") (class "Default")
      (node (ref "U$2") (pin "1") (pinfunction "DAT2_1") (pintype "bidirectional"))
    )
    (net (code "138") (name "unconnected-(U$2-PadCD)") (class "Default")
      (node (ref "U$2") (pin "CD") (pinfunction "CD_CD") (pintype "bidirectional"))
    )
    (net (code "139") (name "unconnected-(U$3-CTS-Pad23)") (class "Default")
      (node (ref "U$3") (pin "23") (pinfunction "CTS_23") (pintype "bidirectional"))
    )
    (net (code "140") (name "unconnected-(U$3-DCD-Pad1)") (class "Default")
      (node (ref "U$3") (pin "1") (pinfunction "DCD_1") (pintype "bidirectional"))
    )
    (net (code "141") (name "unconnected-(U$3-DSR-Pad27)") (class "Default")
      (node (ref "U$3") (pin "27") (pinfunction "DSR_27") (pintype "bidirectional"))
    )
    (net (code "142") (name "unconnected-(U$3-DTR-Pad28)") (class "Default")
      (node (ref "U$3") (pin "28") (pinfunction "DTR_28") (pintype "bidirectional"))
    )
    (net (code "143") (name "unconnected-(U$3-G1-PadG2)") (class "Default")
      (node (ref "U$3") (pin "G2") (pinfunction "G1_G2") (pintype "bidirectional"))
    )
    (net (code "144") (name "unconnected-(U$3-G2-PadG1)") (class "Default")
      (node (ref "U$3") (pin "G1") (pinfunction "G2_G1") (pintype "bidirectional"))
    )
    (net (code "145") (name "unconnected-(U$3-RI-Pad2)") (class "Default")
      (node (ref "U$3") (pin "2") (pinfunction "RI_2") (pintype "bidirectional"))
    )
    (net (code "146") (name "unconnected-(U$3-RTS-Pad24)") (class "Default")
      (node (ref "U$3") (pin "24") (pinfunction "RTS_24") (pintype "bidirectional"))
    )
    (net (code "147") (name "unconnected-(U$3-SUSPEND-Pad12)") (class "Default")
      (node (ref "U$3") (pin "12") (pinfunction "SUSPEND_12") (pintype "bidirectional"))
    )
    (net (code "148") (name "unconnected-(U$3-~{RST}-Pad9)") (class "Default")
      (node (ref "U$3") (pin "9") (pinfunction "~{RST}_9") (pintype "bidirectional"))
    )
    (net (code "149") (name "unconnected-(U$3-~{SUSPEND}-Pad11)") (class "Default")
      (node (ref "U$3") (pin "11") (pinfunction "~{SUSPEND}_11") (pintype "bidirectional"))
    )
    (net (code "150") (name "unconnected-(U$4C-GPIO0-Pad10)") (class "Default")
      (node (ref "U$4") (pin "10") (pinfunction "GPIO0_10") (pintype "output"))
    )
    (net (code "151") (name "unconnected-(U$4C-GPIO1-Pad9)") (class "Default")
      (node (ref "U$4") (pin "9") (pinfunction "GPIO1_9") (pintype "output"))
    )
    (net (code "152") (name "unconnected-(U$4C-GPIO2-Pad7)") (class "Default")
      (node (ref "U$4") (pin "7") (pinfunction "GPIO2_7") (pintype "bidirectional"))
    )
    (net (code "153") (name "unconnected-(U$4C-GPIO3-Pad6)") (class "Default")
      (node (ref "U$4") (pin "6") (pinfunction "GPIO3_6") (pintype "bidirectional"))
    )
    (net (code "154") (name "unconnected-(U$4C-GPIO4-Pad5)") (class "Default")
      (node (ref "U$4") (pin "5") (pinfunction "GPIO4_5") (pintype "bidirectional"))
    )
    (net (code "155") (name "unconnected-(U$4C-GPIO5-Pad4)") (class "Default")
      (node (ref "U$4") (pin "4") (pinfunction "GPIO5_4") (pintype "bidirectional"))
    )
  )
)
